# 5_unextended_ISO_periferals.net
KiCad netlist of a schematic drawn in Altium Designer
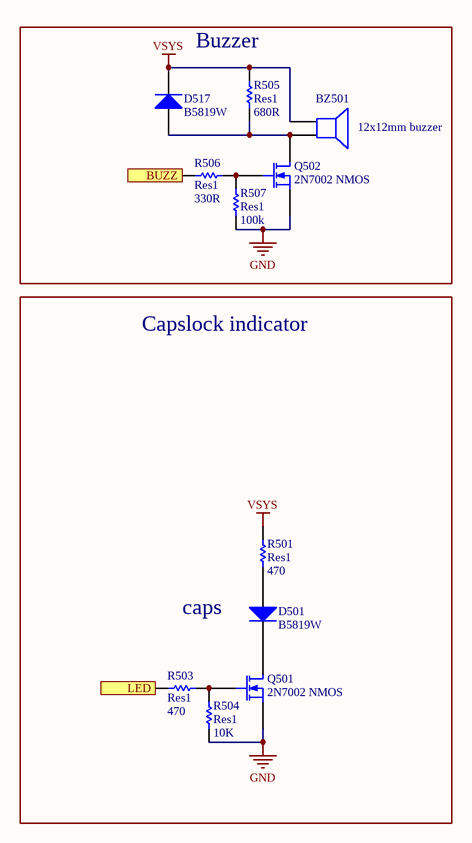
[diagram p0: 5_unextended_ISO_periferals.SchDoc]

(export (version "E")
  (design (tool "Eeschema 10.0.6"))
  (components
    (comp (ref "BZ501")
      (value "12x12mm buzzer")
      (footprint "buzzer 12x12")
      (description "Loudspeaker")
      (fields (field (name "LCSC PART #") "C409829") (field (name "MRF.PART") "YS-SBZ1230"))
      (libsource (lib "Miscellaneous Devices") (part "Speaker"))
    )
    (comp (ref "D501")
      (value "B5819W")
      (footprint "MX-switch - CAPS - LED NO SWITCH")
      (description "Default Diode")
      (libsource (lib "Miscellaneous Devices") (part "Diode"))
    )
    (comp (ref "D517")
      (value "B5819W")
      (footprint "SOD-123")
      (description "Default Diode")
      (fields (field (name "LCSC PART #") "C8598"))
      (libsource (lib "Miscellaneous Devices") (part "Diode"))
    )
    (comp (ref "Q501")
      (value "2N7002 NMOS")
      (footprint "SOT-23-3")
      (description "N-Channel MOSFET")
      (fields (field (name "LCSC PART #") "C8545") (field (name "MRF.PART") "2N7002"))
      (libsource (lib "Miscellaneous Devices") (part "MOSFET-N"))
    )
    (comp (ref "Q502")
      (value "2N7002 NMOS")
      (footprint "SOT-23-3")
      (description "N-Channel MOSFET")
      (fields (field (name "LCSC PART #") "C8545") (field (name "MRF.PART") "2N7002"))
      (libsource (lib "Miscellaneous Devices") (part "MOSFET-N"))
    )
    (comp (ref "R501")
      (value "Res1")
      (footprint "R0603[1608]")
      (description "Resistor")
      (fields
        (field (name "ALTIUM_VALUE") "470")
        (field (name "MFG") "Panasonic Electronic Components")
        (field (name "LCSC PART #") "C23179")
      )
      (libsource (lib "Miscellaneous Devices") (part "Res1"))
    )
    (comp (ref "R503")
      (value "Res1")
      (footprint "R0603[1608]")
      (description "Resistor")
      (fields
        (field (name "ALTIUM_VALUE") "470")
        (field (name "MFG") "Panasonic Electronic Components")
        (field (name "LCSC PART #") "C23179")
      )
      (libsource (lib "Miscellaneous Devices") (part "Res1"))
    )
    (comp (ref "R504")
      (value "Res1")
      (footprint "R0603[1608]")
      (description "Resistor")
      (fields
        (field (name "ALTIUM_VALUE") "10K")
        (field (name "MFG") "Panasonic Electronic Components")
        (field (name "LCSC PART #") "C25804")
      )
      (libsource (lib "Miscellaneous Devices") (part "Res1"))
    )
    (comp (ref "R505")
      (value "Res1")
      (footprint "R0603[1608]")
      (description "Resistor")
      (fields
        (field (name "ALTIUM_VALUE") "680R")
        (field (name "MRF.PART") "0603WAF6800T5E")
        (field (name "LCSC PART #") "C23228")
      )
      (libsource (lib "Miscellaneous Devices") (part "Res1"))
    )
    (comp (ref "R506")
      (value "Res1")
      (footprint "R0603[1608]")
      (description "Resistor")
      (fields
        (field (name "ALTIUM_VALUE") "330R")
        (field (name "LCSC PART #") "C23138")
        (field (name "MRF.PART") "0603WAF3300T5E")
      )
      (libsource (lib "Miscellaneous Devices") (part "Res1"))
    )
    (comp (ref "R507")
      (value "Res1")
      (footprint "R0603[1608]")
      (description "Resistor")
      (fields
        (field (name "ALTIUM_VALUE") "100k")
        (field (name "MRF.PART") "0603WAF1003T5E")
        (field (name "LCSC PART #") "C25803")
      )
      (libsource (lib "Miscellaneous Devices") (part "Res1"))
    )
  )
  (nets
    (net (code "1") (name "/BUZZ") (class "Default")
      (node (ref "R506") (pin "2") (pinfunction "2_2") (pintype "passive"))
    )
    (net (code "2") (name "/LED") (class "Default")
      (node (ref "R503") (pin "1") (pinfunction "1_1") (pintype "passive"))
    )
    (net (code "3") (name "GND") (class "Default")
      (node (ref "Q501") (pin "2") (pinfunction "S_2") (pintype "passive"))
      (node (ref "Q502") (pin "2") (pinfunction "S_2") (pintype "passive"))
      (node (ref "R504") (pin "2") (pinfunction "2_2") (pintype "passive"))
      (node (ref "R507") (pin "2") (pinfunction "2_2") (pintype "passive"))
    )
    (net (code "4") (name "Net-(D501-A)") (class "Default")
      (node (ref "D501") (pin "1") (pinfunction "A_1") (pintype "passive"))
      (node (ref "R501") (pin "1") (pinfunction "1_1") (pintype "passive"))
    )
    (net (code "5") (name "Net-(D501-K)") (class "Default")
      (node (ref "D501") (pin "2") (pinfunction "K_2") (pintype "passive"))
      (node (ref "Q501") (pin "3") (pinfunction "D_3") (pintype "passive"))
    )
    (net (code "6") (name "Net-(D517-A)") (class "Default")
      (node (ref "BZ501") (pin "2") (pinfunction "2_2") (pintype "passive"))
      (node (ref "D517") (pin "1") (pinfunction "A_1") (pintype "passive"))
      (node (ref "Q502") (pin "3") (pinfunction "D_3") (pintype "passive"))
      (node (ref "R505") (pin "2") (pinfunction "2_2") (pintype "passive"))
    )
    (net (code "7") (name "Net-(Q501-G)") (class "Default")
      (node (ref "Q501") (pin "1") (pinfunction "G_1") (pintype "passive"))
      (node (ref "R503") (pin "2") (pinfunction "2_2") (pintype "passive"))
      (node (ref "R504") (pin "1") (pinfunction "1_1") (pintype "passive"))
    )
    (net (code "8") (name "Net-(Q502-G)") (class "Default")
      (node (ref "Q502") (pin "1") (pinfunction "G_1") (pintype "passive"))
      (node (ref "R506") (pin "1") (pinfunction "1_1") (pintype "passive"))
      (node (ref "R507") (pin "1") (pinfunction "1_1") (pintype "passive"))
    )
    (net (code "9") (name "VSYS") (class "Default")
      (node (ref "BZ501") (pin "1") (pinfunction "1_1") (pintype "passive"))
      (node (ref "D517") (pin "2") (pinfunction "K_2") (pintype "passive"))
      (node (ref "R501") (pin "2") (pinfunction "2_2") (pintype "passive"))
      (node (ref "R505") (pin "1") (pinfunction "1_1") (pintype "passive"))
    )
  )
)
